# Input.net
KiCad netlist of a schematic drawn in Altium Designer
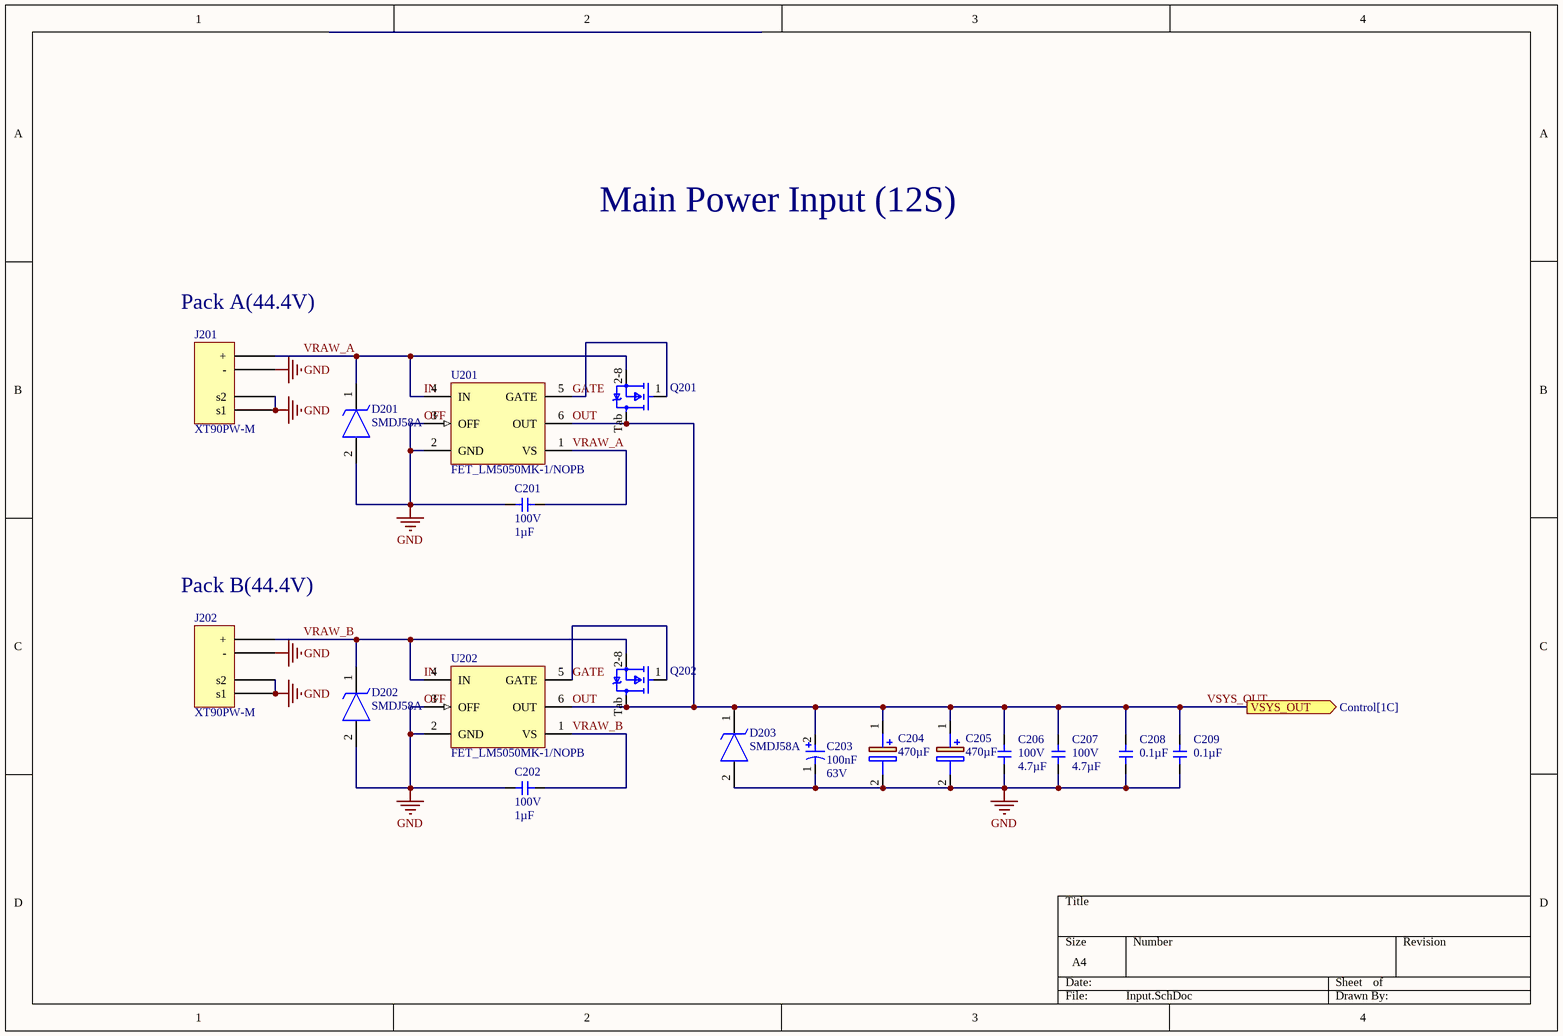
[diagram p0: Input.SchDoc]

(export (version "E")
  (design (tool "Eeschema 10.0.6"))
  (components
    (comp (ref "C201")
      (value "non-polar_Capacitor")
      (footprint "1206")
      (description "SMD type ceramic capacitor")
      (fields
        (field (name "VOLTAGE") "100V")
        (field (name "CAPACITANCE") "1µF")
        (field (name "SOURCE") "robit_passive.SchLib")
      )
      (libsource (lib "robit circuit") (part "Capacitor"))
    )
    (comp (ref "C202")
      (value "non-polar_Capacitor")
      (footprint "1206")
      (description "SMD type ceramic capacitor")
      (fields
        (field (name "VOLTAGE") "100V")
        (field (name "CAPACITANCE") "1µF")
        (field (name "SOURCE") "robit_passive.SchLib")
      )
      (libsource (lib "robit circuit") (part "Capacitor"))
    )
    (comp (ref "C203")
      (value "Capacitor_tantal")
      (footprint "SMD_Capacitor_tantal")
      (description "SMD type tantalum capacitor")
      (fields
        (field (name "CAPACITANCE") "100nF")
        (field (name "VOLTAGE") "63V")
        (field (name "SOURCE") "robit_passive.SchLib")
      )
      (libsource (lib "robit circuit") (part "Capacitor_tantal"))
    )
    (comp (ref "C204")
      (value "470µF")
      (footprint "SamacSys:CAPAE1900X2200N")
      (description "Capacitor Polarised")
      (fields
        (field (name "MANUFACTURER_PART_NUMBER") "MAL215099913E3")
        (field (name "MOUSER PART NUMBER") "594-MAL215099913E3")
      )
      (libsource (lib "*") (part "MAL215099913E3"))
    )
    (comp (ref "C205")
      (value "470µF")
      (footprint "SamacSys:CAPAE1900X2200N")
      (description "Capacitor Polarised")
      (fields
        (field (name "MANUFACTURER_PART_NUMBER") "MAL215099913E3")
        (field (name "MOUSER PART NUMBER") "594-MAL215099913E3")
      )
      (libsource (lib "*") (part "MAL215099913E3"))
    )
    (comp (ref "C206")
      (value "non-polar_Capacitor")
      (footprint "1210")
      (description "SMD type ceramic capacitor")
      (fields
        (field (name "VOLTAGE") "100V")
        (field (name "CAPACITANCE") "4.7µF")
        (field (name "SOURCE") "robit_passive.SchLib")
      )
      (libsource (lib "robit circuit") (part "Capacitor"))
    )
    (comp (ref "C207")
      (value "non-polar_Capacitor")
      (footprint "1210")
      (description "SMD type ceramic capacitor")
      (fields
        (field (name "VOLTAGE") "100V")
        (field (name "CAPACITANCE") "4.7µF")
        (field (name "SOURCE") "robit_passive.SchLib")
      )
      (libsource (lib "robit circuit") (part "Capacitor"))
    )
    (comp (ref "C208")
      (value "non-polar_Capacitor")
      (footprint "0603")
      (description "SMD type ceramic capacitor")
      (fields
        (field (name "VOLTAGE") "100V")
        (field (name "CAPACITANCE") "0.1µF")
        (field (name "SOURCE") "robit_passive.SchLib")
      )
      (libsource (lib "robit circuit") (part "Capacitor"))
    )
    (comp (ref "C209")
      (value "non-polar_Capacitor")
      (footprint "0603")
      (description "SMD type ceramic capacitor")
      (fields
        (field (name "VOLTAGE") "100V")
        (field (name "CAPACITANCE") "0.1µF")
        (field (name "SOURCE") "robit_passive.SchLib")
      )
      (libsource (lib "robit circuit") (part "Capacitor"))
    )
    (comp (ref "D201")
      (value "SMDJ58A")
      (footprint "SamacSys:DIONM7959X262N")
      (description "TVS Diode (Uni-directional)")
      (fields (field (name "MOUSER PART NUMBER") "576-SMDJ58A"))
      (libsource (lib "*") (part "SMDJ58A"))
    )
    (comp (ref "D202")
      (value "SMDJ58A")
      (footprint "SamacSys:DIONM7959X262N")
      (description "TVS Diode (Uni-directional)")
      (fields (field (name "MOUSER PART NUMBER") "576-SMDJ58A"))
      (libsource (lib "*") (part "SMDJ58A"))
    )
    (comp (ref "D203")
      (value "SMDJ58A")
      (footprint "SamacSys:DIONM7959X262N")
      (description "TVS Diode (Uni-directional)")
      (fields (field (name "MOUSER PART NUMBER") "576-SMDJ58A"))
      (libsource (lib "*") (part "SMDJ58A"))
    )
    (comp (ref "J201")
      (value "XT90PW-M")
      (footprint "AMASS_XT90PW-M")
      (description "Socket; DC supply; XT90; male; PIN: 2; on PCBs; THT; Colour: yellow")
      (fields (field (name "MF") "AMASS"))
      (libsource (lib "robit circuit") (part "XT90PW-M"))
    )
    (comp (ref "J202")
      (value "XT90PW-M")
      (footprint "AMASS_XT90PW-M")
      (description "Socket; DC supply; XT90; male; PIN: 2; on PCBs; THT; Colour: yellow")
      (fields (field (name "MF") "AMASS"))
      (libsource (lib "robit circuit") (part "XT90PW-M"))
    )
    (comp (ref "Q201")
      (value "Trans_Infineon_IPT015N10N5_eec")
      (footprint "Infineon_IPT015N10N5_0")
      (description "TRANS MOSFET N-CH 100V 300A 8HSOF")
      (fields (field (name "PART NUMBER") "IPT015N10N5") (field (name "MANUFACTURER") "Infineon"))
      (libsource (lib "Trans_Infineon_IPT015N10N5_eec") (part "Trans_Infineon_IPT015N10N5_eec"))
    )
    (comp (ref "Q202")
      (value "Trans_Infineon_IPT015N10N5_eec")
      (footprint "Infineon_IPT015N10N5_0")
      (description "TRANS MOSFET N-CH 100V 300A 8HSOF")
      (fields (field (name "PART NUMBER") "IPT015N10N5") (field (name "MANUFACTURER") "Infineon"))
      (libsource (lib "Trans_Infineon_IPT015N10N5_eec") (part "Trans_Infineon_IPT015N10N5_eec"))
    )
    (comp (ref "U201")
      (value "FET_LM5050MK-1/NOPB")
      (footprint "DDC0006A_M")
      (description "5-V to 75-V 400-uA IQ ORing FET controller 6-SOT-23-THIN -40 to 125")
      (libsource (lib "robit circuit") (part "PM-SMPS-LM5050-IL6"))
    )
    (comp (ref "U202")
      (value "FET_LM5050MK-1/NOPB")
      (footprint "DDC0006A_M")
      (description "5-V to 75-V 400-uA IQ ORing FET controller 6-SOT-23-THIN -40 to 125")
      (libsource (lib "robit circuit") (part "PM-SMPS-LM5050-IL6"))
    )
  )
  (nets
    (net (code "1") (name "/GATE") (class "Default")
      (node (ref "Q201") (pin "1") (pinfunction "Gate_1") (pintype "passive"))
      (node (ref "Q202") (pin "1") (pinfunction "Gate_1") (pintype "passive"))
      (node (ref "U201") (pin "5") (pinfunction "GATE_5") (pintype "power_in"))
      (node (ref "U202") (pin "5") (pinfunction "GATE_5") (pintype "power_in"))
    )
    (net (code "2") (name "/IN") (class "Default")
      (node (ref "C201") (pin "2") (pinfunction "2_2") (pintype "passive"))
      (node (ref "C202") (pin "2") (pinfunction "2_2") (pintype "passive"))
      (node (ref "D201") (pin "1") (pinfunction "K_1") (pintype "passive"))
      (node (ref "D202") (pin "1") (pinfunction "K_1") (pintype "passive"))
      (node (ref "J201") (pin "P") (pinfunction "+_P") (pintype "power_in"))
      (node (ref "J202") (pin "P") (pinfunction "+_P") (pintype "power_in"))
      (node (ref "Q201") (pin "2-8") (pinfunction "Source_2-8") (pintype "passive"))
      (node (ref "Q202") (pin "2-8") (pinfunction "Source_2-8") (pintype "passive"))
      (node (ref "U201") (pin "1") (pinfunction "VS_1") (pintype "power_in"))
      (node (ref "U201") (pin "4") (pinfunction "IN_4") (pintype "power_in"))
      (node (ref "U202") (pin "1") (pinfunction "VS_1") (pintype "power_in"))
      (node (ref "U202") (pin "4") (pinfunction "IN_4") (pintype "power_in"))
    )
    (net (code "3") (name "/OUT") (class "Default")
      (node (ref "C203") (pin "2") (pinfunction "1_2") (pintype "passive"))
      (node (ref "C204") (pin "1") (pinfunction "+_1") (pintype "passive"))
      (node (ref "C205") (pin "1") (pinfunction "+_1") (pintype "passive"))
      (node (ref "C206") (pin "1") (pinfunction "1_1") (pintype "passive"))
      (node (ref "C207") (pin "2") (pinfunction "2_2") (pintype "passive"))
      (node (ref "C208") (pin "2") (pinfunction "2_2") (pintype "passive"))
      (node (ref "C209") (pin "2") (pinfunction "2_2") (pintype "passive"))
      (node (ref "D203") (pin "1") (pinfunction "K_1") (pintype "passive"))
      (node (ref "Q201") (pin "Tab") (pinfunction "Drain_Tab") (pintype "passive"))
      (node (ref "Q202") (pin "Tab") (pinfunction "Drain_Tab") (pintype "passive"))
      (node (ref "U201") (pin "6") (pinfunction "OUT_6") (pintype "power_in"))
      (node (ref "U202") (pin "6") (pinfunction "OUT_6") (pintype "power_in"))
    )
    (net (code "4") (name "GND") (class "Default")
      (node (ref "C201") (pin "1") (pinfunction "1_1") (pintype "passive"))
      (node (ref "C202") (pin "1") (pinfunction "1_1") (pintype "passive"))
      (node (ref "C203") (pin "1") (pinfunction "0_1") (pintype "passive"))
      (node (ref "C204") (pin "2") (pinfunction "-_2") (pintype "passive"))
      (node (ref "C205") (pin "2") (pinfunction "-_2") (pintype "passive"))
      (node (ref "C206") (pin "2") (pinfunction "2_2") (pintype "passive"))
      (node (ref "C207") (pin "1") (pinfunction "1_1") (pintype "passive"))
      (node (ref "C208") (pin "1") (pinfunction "1_1") (pintype "passive"))
      (node (ref "C209") (pin "1") (pinfunction "1_1") (pintype "passive"))
      (node (ref "D201") (pin "2") (pinfunction "A_2") (pintype "passive"))
      (node (ref "D202") (pin "2") (pinfunction "A_2") (pintype "passive"))
      (node (ref "D203") (pin "2") (pinfunction "A_2") (pintype "passive"))
      (node (ref "J201") (pin "N") (pinfunction "-_N") (pintype "power_in"))
      (node (ref "J201") (pin "S1") (pinfunction "s1_S1") (pintype "power_in"))
      (node (ref "J201") (pin "S2") (pinfunction "s2_S2") (pintype "power_in"))
      (node (ref "J202") (pin "N") (pinfunction "-_N") (pintype "power_in"))
      (node (ref "J202") (pin "S1") (pinfunction "s1_S1") (pintype "power_in"))
      (node (ref "J202") (pin "S2") (pinfunction "s2_S2") (pintype "power_in"))
      (node (ref "U201") (pin "2") (pinfunction "GND_2") (pintype "power_in"))
      (node (ref "U201") (pin "3") (pinfunction "OFF_3") (pintype "input"))
      (node (ref "U202") (pin "2") (pinfunction "GND_2") (pintype "power_in"))
      (node (ref "U202") (pin "3") (pinfunction "OFF_3") (pintype "input"))
    )
  )
)
